# craw.net
KiCad netlist of a schematic drawn in EAGLE
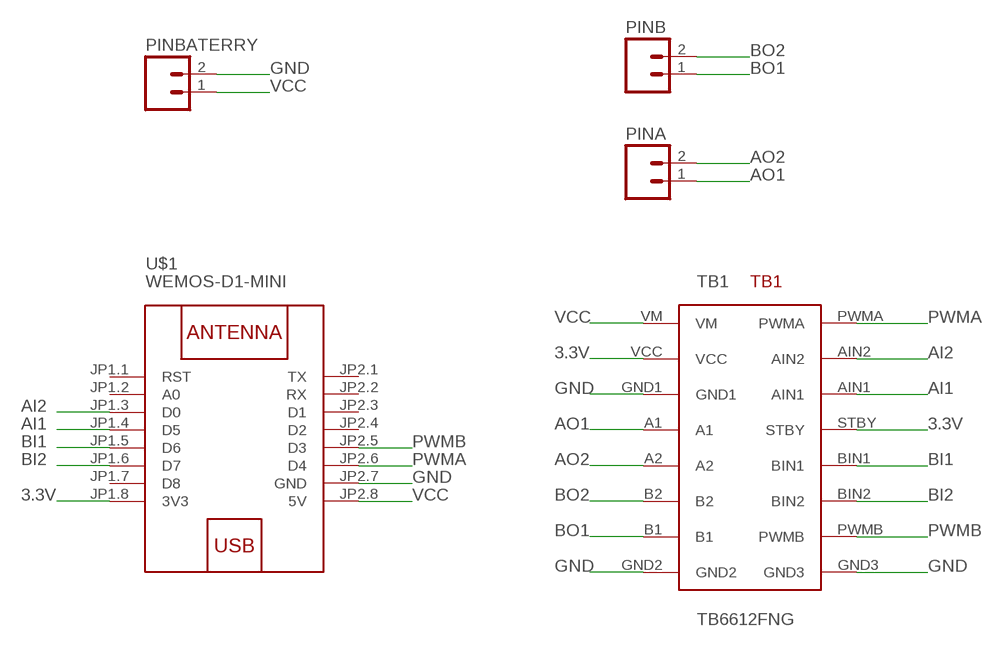
[diagram p0: schematic, sheet 1]

(export (version "E")
  (design (tool "Eeschema 10.0.6"))
  (components
    (comp (ref "PINA")
      (value "M02")
      (footprint "eagle-import:02P")
      (libsource (lib "eagle-import") (part "M02"))
    )
    (comp (ref "PINB")
      (value "M02")
      (footprint "eagle-import:02P")
      (libsource (lib "eagle-import") (part "M02"))
    )
    (comp (ref "PINBATERRY")
      (value "M02")
      (footprint "eagle-import:02P")
      (libsource (lib "eagle-import") (part "M02"))
    )
    (comp (ref "TB1")
      (value "TB6612FNG")
      (footprint "eagle-import:TB6612FNG")
      (libsource (lib "eagle-import") (part "TB6612FNG"))
    )
    (comp (ref "U$1")
      (value "WEMOS-D1-MINI")
      (footprint "eagle-import:WEMOS-D1-MINI")
      (libsource (lib "eagle-import") (part "WEMOS-D1-MINI"))
    )
  )
  (nets
    (net (code "1") (name "/3.3V") (class "Default")
      (node (ref "TB1") (pin "STBY") (pinfunction "STBY_STBY") (pintype "bidirectional"))
      (node (ref "TB1") (pin "VCC") (pinfunction "VCC_VCC") (pintype "bidirectional"))
      (node (ref "U$1") (pin "JP1.8") (pinfunction "3V3_JP1.8") (pintype "power_in"))
    )
    (net (code "2") (name "/AI1") (class "Default")
      (node (ref "TB1") (pin "AIN1") (pinfunction "AIN1_AIN1") (pintype "bidirectional"))
      (node (ref "U$1") (pin "JP1.4") (pinfunction "D5_JP1.4") (pintype "bidirectional"))
    )
    (net (code "3") (name "/AI2") (class "Default")
      (node (ref "TB1") (pin "AIN2") (pinfunction "AIN2_AIN2") (pintype "bidirectional"))
      (node (ref "U$1") (pin "JP1.3") (pinfunction "D0_JP1.3") (pintype "bidirectional"))
    )
    (net (code "4") (name "/AO1") (class "Default")
      (node (ref "PINA") (pin "1") (pinfunction "1_1") (pintype "passive"))
      (node (ref "TB1") (pin "A1") (pinfunction "A1_A1") (pintype "bidirectional"))
    )
    (net (code "5") (name "/AO2") (class "Default")
      (node (ref "PINA") (pin "2") (pinfunction "2_2") (pintype "passive"))
      (node (ref "TB1") (pin "A2") (pinfunction "A2_A2") (pintype "bidirectional"))
    )
    (net (code "6") (name "/BI1") (class "Default")
      (node (ref "TB1") (pin "BIN1") (pinfunction "BIN1_BIN1") (pintype "bidirectional"))
      (node (ref "U$1") (pin "JP1.5") (pinfunction "D6_JP1.5") (pintype "bidirectional"))
    )
    (net (code "7") (name "/BI2") (class "Default")
      (node (ref "TB1") (pin "BIN2") (pinfunction "BIN2_BIN2") (pintype "bidirectional"))
      (node (ref "U$1") (pin "JP1.6") (pinfunction "D7_JP1.6") (pintype "bidirectional"))
    )
    (net (code "8") (name "/BO1") (class "Default")
      (node (ref "PINB") (pin "1") (pinfunction "1_1") (pintype "passive"))
      (node (ref "TB1") (pin "B1") (pinfunction "B1_B1") (pintype "bidirectional"))
    )
    (net (code "9") (name "/BO2") (class "Default")
      (node (ref "PINB") (pin "2") (pinfunction "2_2") (pintype "passive"))
      (node (ref "TB1") (pin "B2") (pinfunction "B2_B2") (pintype "bidirectional"))
    )
    (net (code "10") (name "/GND") (class "Default")
      (node (ref "PINBATERRY") (pin "2") (pinfunction "2_2") (pintype "passive"))
      (node (ref "TB1") (pin "GND1") (pinfunction "GND1_GND1") (pintype "bidirectional"))
      (node (ref "TB1") (pin "GND2") (pinfunction "GND2_GND2") (pintype "bidirectional"))
      (node (ref "TB1") (pin "GND3") (pinfunction "GND3_GND3") (pintype "bidirectional"))
      (node (ref "U$1") (pin "JP2.7") (pinfunction "GND_JP2.7") (pintype "power_in"))
    )
    (net (code "11") (name "/PWMA") (class "Default")
      (node (ref "TB1") (pin "PWMA") (pinfunction "PWMA_PWMA") (pintype "bidirectional"))
      (node (ref "U$1") (pin "JP2.6") (pinfunction "D4_JP2.6") (pintype "bidirectional"))
    )
    (net (code "12") (name "/PWMB") (class "Default")
      (node (ref "TB1") (pin "PWMB") (pinfunction "PWMB_PWMB") (pintype "bidirectional"))
      (node (ref "U$1") (pin "JP2.5") (pinfunction "D3_JP2.5") (pintype "bidirectional"))
    )
    (net (code "13") (name "/VCC") (class "Default")
      (node (ref "PINBATERRY") (pin "1") (pinfunction "1_1") (pintype "passive"))
      (node (ref "TB1") (pin "VM") (pinfunction "VM_VM") (pintype "bidirectional"))
      (node (ref "U$1") (pin "JP2.8") (pinfunction "5V_JP2.8") (pintype "power_in"))
    )
    (net (code "14") (name "unconnected-(U$1-A0-PadJP1.2)") (class "Default")
      (node (ref "U$1") (pin "JP1.2") (pinfunction "A0_JP1.2") (pintype "bidirectional"))
    )
    (net (code "15") (name "unconnected-(U$1-D1-PadJP2.3)") (class "Default")
      (node (ref "U$1") (pin "JP2.3") (pinfunction "D1_JP2.3") (pintype "bidirectional"))
    )
    (net (code "16") (name "unconnected-(U$1-D2-PadJP2.4)") (class "Default")
      (node (ref "U$1") (pin "JP2.4") (pinfunction "D2_JP2.4") (pintype "bidirectional"))
    )
    (net (code "17") (name "unconnected-(U$1-D8-PadJP1.7)") (class "Default")
      (node (ref "U$1") (pin "JP1.7") (pinfunction "D8_JP1.7") (pintype "bidirectional"))
    )
    (net (code "18") (name "unconnected-(U$1-RST-PadJP1.1)") (class "Default")
      (node (ref "U$1") (pin "JP1.1") (pinfunction "RST_JP1.1") (pintype "bidirectional"))
    )
    (net (code "19") (name "unconnected-(U$1-RX-PadJP2.2)") (class "Default")
      (node (ref "U$1") (pin "JP2.2") (pinfunction "RX_JP2.2") (pintype "bidirectional"))
    )
    (net (code "20") (name "unconnected-(U$1-TX-PadJP2.1)") (class "Default")
      (node (ref "U$1") (pin "JP2.1") (pinfunction "TX_JP2.1") (pintype "bidirectional"))
    )
  )
)
